# Connectors.net
KiCad netlist of a schematic drawn in Altium Designer
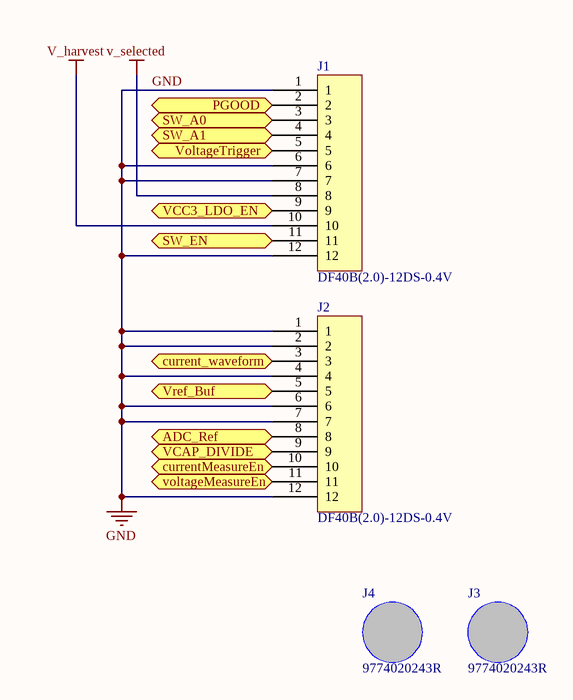
[diagram p0: Connectors.SchDoc]

(export (version "E")
  (design (tool "Eeschema 10.0.6"))
  (components
    (comp (ref "J1")
      (value "DF40B(2.0)-12DS-0.4V")
      (footprint "DF40B(2.0)-12DS-0.4V")
      (description "Hirose BM20 Series, 0.4mm pitch, 2mm stack height, 12 pos, header")
      (libsource (lib "connectors") (part "DF40B(2.0)-12DS-0.4V"))
    )
    (comp (ref "J2")
      (value "DF40B(2.0)-12DS-0.4V")
      (footprint "DF40B(2.0)-12DS-0.4V")
      (description "Hirose BM20 Series, 0.4mm pitch, 2mm stack height, 12 pos, header")
      (libsource (lib "connectors") (part "DF40B(2.0)-12DS-0.4V"))
    )
    (comp (ref "J3")
      (value "9774020243R")
      (footprint "9774020243R")
      (description "2 mm stack height, m2 standoff")
      (libsource (lib "connectors") (part "9774020243R"))
    )
    (comp (ref "J4")
      (value "9774020243R")
      (footprint "9774020243R")
      (description "2 mm stack height, m2 standoff")
      (libsource (lib "connectors") (part "9774020243R"))
    )
  )
  (nets
    (net (code "1") (name "/ADC_Ref") (class "Default")
      (node (ref "J2") (pin "8") (pinfunction "8_8") (pintype "passive"))
    )
    (net (code "2") (name "/PGOOD") (class "Default")
      (node (ref "J1") (pin "2") (pinfunction "2_2") (pintype "passive"))
    )
    (net (code "3") (name "/SW_A0") (class "Default")
      (node (ref "J1") (pin "3") (pinfunction "3_3") (pintype "passive"))
    )
    (net (code "4") (name "/SW_A1") (class "Default")
      (node (ref "J1") (pin "4") (pinfunction "4_4") (pintype "passive"))
    )
    (net (code "5") (name "/SW_EN") (class "Default")
      (node (ref "J1") (pin "11") (pinfunction "11_11") (pintype "passive"))
    )
    (net (code "6") (name "/VCAP_DIVIDE") (class "Default")
      (node (ref "J2") (pin "9") (pinfunction "9_9") (pintype "passive"))
    )
    (net (code "7") (name "/VCC3_LDO_EN") (class "Default")
      (node (ref "J1") (pin "9") (pinfunction "9_9") (pintype "passive"))
    )
    (net (code "8") (name "/VoltageTrigger") (class "Default")
      (node (ref "J1") (pin "5") (pinfunction "5_5") (pintype "passive"))
    )
    (net (code "9") (name "/Vref_Buf") (class "Default")
      (node (ref "J2") (pin "5") (pinfunction "5_5") (pintype "passive"))
    )
    (net (code "10") (name "/currentMeasureEn") (class "Default")
      (node (ref "J2") (pin "10") (pinfunction "10_10") (pintype "passive"))
    )
    (net (code "11") (name "/current_waveform") (class "Default")
      (node (ref "J2") (pin "3") (pinfunction "3_3") (pintype "passive"))
    )
    (net (code "12") (name "/voltageMeasureEn") (class "Default")
      (node (ref "J2") (pin "11") (pinfunction "11_11") (pintype "passive"))
    )
    (net (code "13") (name "GND") (class "Default")
      (node (ref "J1") (pin "1") (pinfunction "1_1") (pintype "passive"))
      (node (ref "J1") (pin "12") (pinfunction "12_12") (pintype "passive"))
      (node (ref "J1") (pin "6") (pinfunction "6_6") (pintype "passive"))
      (node (ref "J1") (pin "7") (pinfunction "7_7") (pintype "passive"))
      (node (ref "J2") (pin "1") (pinfunction "1_1") (pintype "passive"))
      (node (ref "J2") (pin "12") (pinfunction "12_12") (pintype "passive"))
      (node (ref "J2") (pin "2") (pinfunction "2_2") (pintype "passive"))
      (node (ref "J2") (pin "4") (pinfunction "4_4") (pintype "passive"))
      (node (ref "J2") (pin "6") (pinfunction "6_6") (pintype "passive"))
      (node (ref "J2") (pin "7") (pinfunction "7_7") (pintype "passive"))
    )
    (net (code "14") (name "V_harvest") (class "Default")
      (node (ref "J1") (pin "10") (pinfunction "10_10") (pintype "passive"))
    )
    (net (code "15") (name "v_selected") (class "Default")
      (node (ref "J1") (pin "8") (pinfunction "8_8") (pintype "passive"))
    )
  )
)
